# v2.net
KiCad netlist of a schematic drawn in EAGLE
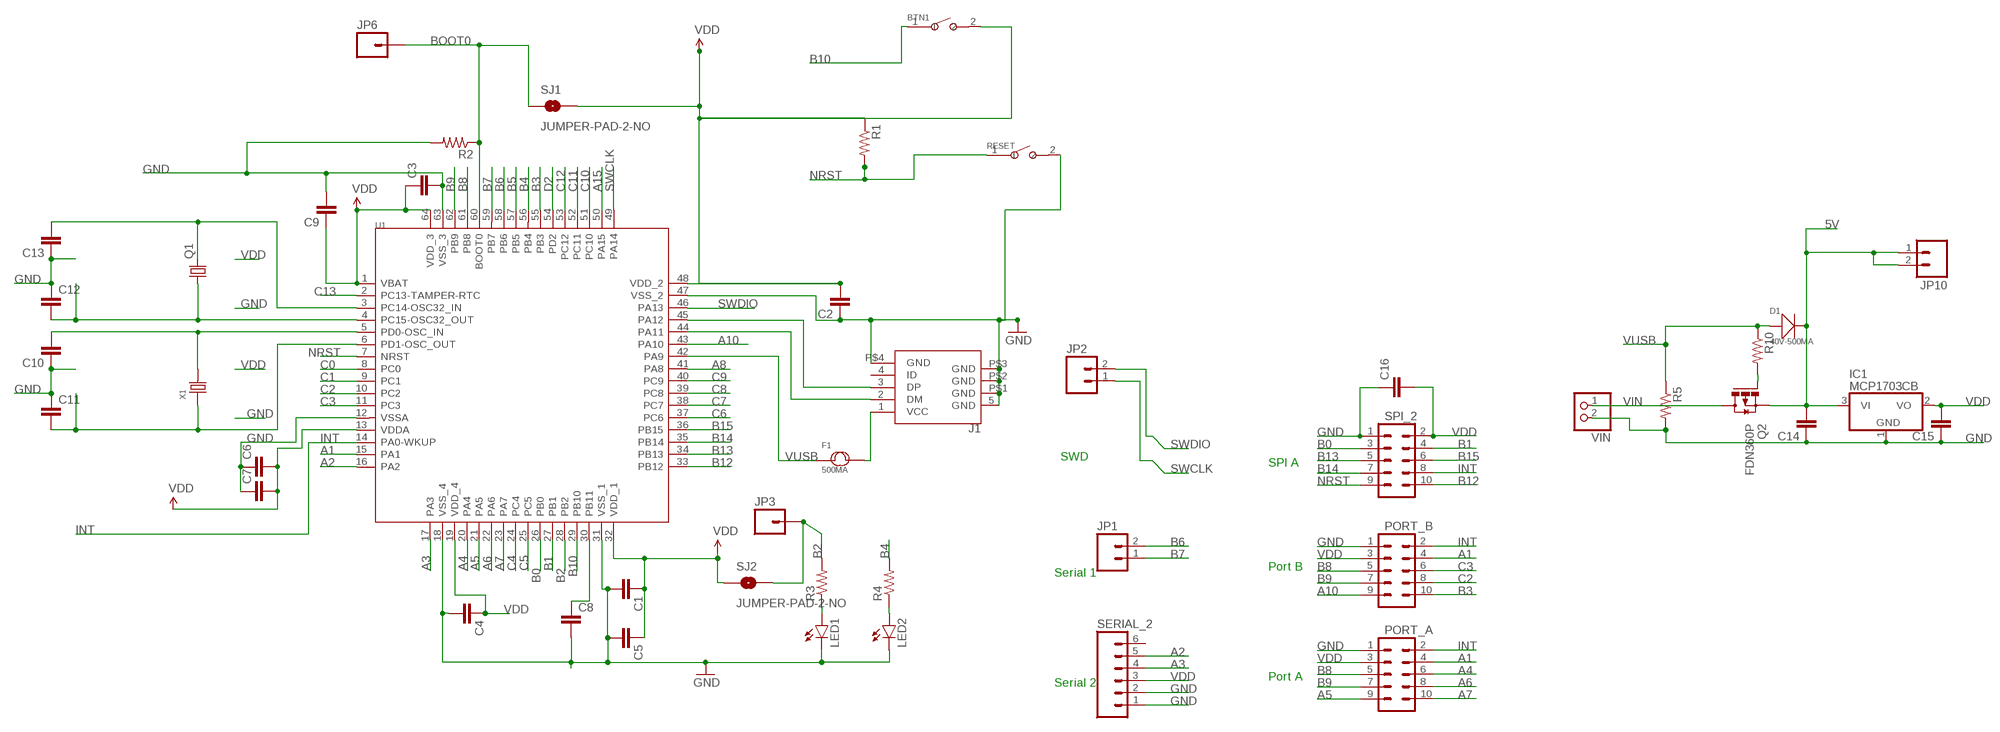
[diagram p0: schematic, sheet 1]

(export (version "E")
  (design (tool "Eeschema 10.0.6"))
  (components
    (comp (ref "BTN1")
      (value "SMD-BUTTON(2P-6.0X3.0X2.5MM)-DHT-1163S")
      (footprint "eagle-import:SW2-4.0-6.0X3.0X2.5MM")
      (libsource (lib "eagle-import") (part "SMD-BUTTON(2P-6.0X3.0X2.5MM)-DHT-1163S"))
    )
    (comp (ref "C1")
      (value "CAP0805")
      (footprint "eagle-import:0805")
      (libsource (lib "eagle-import") (part "CAP0805"))
    )
    (comp (ref "C2")
      (value "CAP0805")
      (footprint "eagle-import:0805")
      (libsource (lib "eagle-import") (part "CAP0805"))
    )
    (comp (ref "C3")
      (value "CAP0805")
      (footprint "eagle-import:0805")
      (libsource (lib "eagle-import") (part "CAP0805"))
    )
    (comp (ref "C4")
      (value "CAP0805")
      (footprint "eagle-import:0805")
      (libsource (lib "eagle-import") (part "CAP0805"))
    )
    (comp (ref "C5")
      (value "CAP0805")
      (footprint "eagle-import:0805")
      (libsource (lib "eagle-import") (part "CAP0805"))
    )
    (comp (ref "C6")
      (value "CAP0805")
      (footprint "eagle-import:0805")
      (libsource (lib "eagle-import") (part "CAP0805"))
    )
    (comp (ref "C7")
      (value "CAP0805")
      (footprint "eagle-import:0805")
      (libsource (lib "eagle-import") (part "CAP0805"))
    )
    (comp (ref "C8")
      (value "CAP0805")
      (footprint "eagle-import:0805")
      (libsource (lib "eagle-import") (part "CAP0805"))
    )
    (comp (ref "C9")
      (value "CAP0805")
      (footprint "eagle-import:0805")
      (libsource (lib "eagle-import") (part "CAP0805"))
    )
    (comp (ref "C10")
      (value "CAP0805")
      (footprint "eagle-import:0805")
      (libsource (lib "eagle-import") (part "CAP0805"))
    )
    (comp (ref "C11")
      (value "CAP0805")
      (footprint "eagle-import:0805")
      (libsource (lib "eagle-import") (part "CAP0805"))
    )
    (comp (ref "C12")
      (value "CAP0805")
      (footprint "eagle-import:0805")
      (libsource (lib "eagle-import") (part "CAP0805"))
    )
    (comp (ref "C13")
      (value "CAP0805")
      (footprint "eagle-import:0805")
      (libsource (lib "eagle-import") (part "CAP0805"))
    )
    (comp (ref "C14")
      (value "CAP0805")
      (footprint "eagle-import:0805")
      (libsource (lib "eagle-import") (part "CAP0805"))
    )
    (comp (ref "C15")
      (value "CAP0805")
      (footprint "eagle-import:0805")
      (libsource (lib "eagle-import") (part "CAP0805"))
    )
    (comp (ref "C16")
      (value "CAP0805")
      (footprint "eagle-import:0805")
      (libsource (lib "eagle-import") (part "CAP0805"))
    )
    (comp (ref "D1")
      (value "40V-500MA")
      (footprint "eagle-import:SOD-123")
      (fields (field (name "MPN") "B0540W"))
      (libsource (lib "eagle-import") (part "SMD-DIODE-SCHOTTKY-40V-500MA(SOD-123)"))
    )
    (comp (ref "F1")
      (value "500MA")
      (footprint "eagle-import:F1206")
      (libsource (lib "eagle-import") (part "SMD-PPTC-500MA(1206)"))
    )
    (comp (ref "IC1")
      (value "MCP1703CB")
      (footprint "eagle-import:SOT23")
      (libsource (lib "eagle-import") (part "MCP1703CB"))
    )
    (comp (ref "J1")
      (value "MINI-USB-RCPT-B-5PS-R/A-SMD(ST-USB-002A)")
      (footprint "eagle-import:MINIUSB5+4P-SMD-0.8-90D")
      (fields (field (name "MPN") "ST-USB-002A"))
      (libsource (lib "eagle-import") (part "MINI-USB-RCPT-B-5PS-R/A-SMD(ST-USB-002A)"))
    )
    (comp (ref "JP1")
      (value "M02PTH")
      (footprint "eagle-import:1X02")
      (libsource (lib "eagle-import") (part "M02PTH"))
    )
    (comp (ref "JP2")
      (value "M02PTH")
      (footprint "eagle-import:1X02")
      (libsource (lib "eagle-import") (part "M02PTH"))
    )
    (comp (ref "JP3")
      (value "M01PTH")
      (footprint "eagle-import:1X01")
      (libsource (lib "eagle-import") (part "M01PTH"))
    )
    (comp (ref "JP6")
      (value "M01PTH")
      (footprint "eagle-import:1X01")
      (libsource (lib "eagle-import") (part "M01PTH"))
    )
    (comp (ref "JP10")
      (value "M02PTH")
      (footprint "eagle-import:1X02")
      (libsource (lib "eagle-import") (part "M02PTH"))
    )
    (comp (ref "LED1")
      (value "LED1206")
      (footprint "eagle-import:LED-1206")
      (libsource (lib "eagle-import") (part "LED1206"))
    )
    (comp (ref "LED2")
      (value "LED1206")
      (footprint "eagle-import:LED-1206")
      (libsource (lib "eagle-import") (part "LED1206"))
    )
    (comp (ref "PORT_A")
      (value "M05X2PTH")
      (footprint "eagle-import:AVR_ICSP")
      (libsource (lib "eagle-import") (part "M05X2PTH"))
    )
    (comp (ref "PORT_B")
      (value "M05X2PTH")
      (footprint "eagle-import:AVR_ICSP")
      (libsource (lib "eagle-import") (part "M05X2PTH"))
    )
    (comp (ref "Q1")
      (value "CRYSTALTC26H")
      (footprint "eagle-import:TC26H")
      (libsource (lib "eagle-import") (part "CRYSTALTC26H"))
    )
    (comp (ref "Q2")
      (value "FDN360P")
      (footprint "eagle-import:SUPER-SOT3")
      (libsource (lib "eagle-import") (part "FDN360P"))
    )
    (comp (ref "R1")
      (value "RESISTOR0805-RES")
      (footprint "eagle-import:0805")
      (libsource (lib "eagle-import") (part "RESISTOR0805-RES"))
    )
    (comp (ref "R2")
      (value "RESISTOR0805-RES")
      (footprint "eagle-import:0805")
      (libsource (lib "eagle-import") (part "RESISTOR0805-RES"))
    )
    (comp (ref "R3")
      (value "RESISTOR0805-RES")
      (footprint "eagle-import:0805")
      (libsource (lib "eagle-import") (part "RESISTOR0805-RES"))
    )
    (comp (ref "R4")
      (value "RESISTOR0805-RES")
      (footprint "eagle-import:0805")
      (libsource (lib "eagle-import") (part "RESISTOR0805-RES"))
    )
    (comp (ref "R5")
      (value "RESISTOR0805-RES")
      (footprint "eagle-import:0805")
      (libsource (lib "eagle-import") (part "RESISTOR0805-RES"))
    )
    (comp (ref "R10")
      (value "RESISTOR0805-RES")
      (footprint "eagle-import:0805")
      (libsource (lib "eagle-import") (part "RESISTOR0805-RES"))
    )
    (comp (ref "RESET")
      (value "SMD-BUTTON(2P-6.0X3.0X2.5MM)-DHT-1163S")
      (footprint "eagle-import:SW2-4.0-6.0X3.0X2.5MM")
      (libsource (lib "eagle-import") (part "SMD-BUTTON(2P-6.0X3.0X2.5MM)-DHT-1163S"))
    )
    (comp (ref "SERIAL_2")
      (value "M06SILK_FEMALE_PTH")
      (footprint "eagle-import:1X06")
      (libsource (lib "eagle-import") (part "M06SILK_FEMALE_PTH"))
    )
    (comp (ref "SJ1")
      (value "JUMPER-PAD-2-NO")
      (footprint "eagle-import:PAD-JUMPER-2-NO_NO_SILK")
      (libsource (lib "eagle-import") (part "JUMPER-PAD-2-NO"))
    )
    (comp (ref "SJ2")
      (value "JUMPER-PAD-2-NO")
      (footprint "eagle-import:PAD-JUMPER-2-NO_NO_SILK")
      (libsource (lib "eagle-import") (part "JUMPER-PAD-2-NO"))
    )
    (comp (ref "SPI_2")
      (value "M05X2PTH")
      (footprint "eagle-import:AVR_ICSP")
      (libsource (lib "eagle-import") (part "M05X2PTH"))
    )
    (comp (ref "U1")
      (value "MCU-STM32F401RBT6(LQFP64)")
      (footprint "eagle-import:LQFP64-0.5-10X10MM")
      (fields (field (name "MPN") "STM32F401RBT6"))
      (libsource (lib "eagle-import") (part "MCU-STM32F401RBT6(LQFP64)"))
    )
    (comp (ref "VIN")
      (value "JST_2PIN-SMT-RA")
      (footprint "eagle-import:JST-PH-2-SMT-RA")
      (libsource (lib "eagle-import") (part "JST_2PIN-SMT-RA"))
    )
    (comp (ref "X1")
      (value "CRYSTAL'HC49US'")
      (footprint "eagle-import:HC49US")
      (libsource (lib "eagle-import") (part "CRYSTAL'HC49US'"))
    )
  )
  (nets
    (net (code "1") (name "/5V") (class "Default")
      (node (ref "C14") (pin "2") (pinfunction "2_2") (pintype "passive"))
      (node (ref "D1") (pin "-") (pinfunction "-_-") (pintype "passive"))
      (node (ref "IC1") (pin "3") (pinfunction "VI_3") (pintype "input"))
      (node (ref "JP10") (pin "1") (pinfunction "1_1") (pintype "passive"))
      (node (ref "JP10") (pin "2") (pinfunction "2_2") (pintype "passive"))
      (node (ref "Q2") (pin "2") (pinfunction "S_2") (pintype "passive"))
    )
    (net (code "2") (name "/A1") (class "Default")
      (node (ref "PORT_A") (pin "4") (pinfunction "4_4") (pintype "passive"))
      (node (ref "PORT_B") (pin "4") (pinfunction "4_4") (pintype "passive"))
      (node (ref "U1") (pin "15") (pinfunction "PA1_15") (pintype "bidirectional"))
    )
    (net (code "3") (name "/A2") (class "Default")
      (node (ref "SERIAL_2") (pin "5") (pinfunction "5_5") (pintype "passive"))
      (node (ref "U1") (pin "16") (pinfunction "PA2_16") (pintype "bidirectional"))
    )
    (net (code "4") (name "/A3") (class "Default")
      (node (ref "SERIAL_2") (pin "4") (pinfunction "4_4") (pintype "passive"))
      (node (ref "U1") (pin "17") (pinfunction "PA3_17") (pintype "bidirectional"))
    )
    (net (code "5") (name "/A4") (class "Default")
      (node (ref "PORT_A") (pin "6") (pinfunction "6_6") (pintype "passive"))
      (node (ref "U1") (pin "20") (pinfunction "PA4_20") (pintype "bidirectional"))
    )
    (net (code "6") (name "/A5") (class "Default")
      (node (ref "PORT_A") (pin "9") (pinfunction "9_9") (pintype "passive"))
      (node (ref "U1") (pin "21") (pinfunction "PA5_21") (pintype "bidirectional"))
    )
    (net (code "7") (name "/A6") (class "Default")
      (node (ref "PORT_A") (pin "8") (pinfunction "8_8") (pintype "passive"))
      (node (ref "U1") (pin "22") (pinfunction "PA6_22") (pintype "bidirectional"))
    )
    (net (code "8") (name "/A7") (class "Default")
      (node (ref "PORT_A") (pin "10") (pinfunction "10_10") (pintype "passive"))
      (node (ref "U1") (pin "23") (pinfunction "PA7_23") (pintype "bidirectional"))
    )
    (net (code "9") (name "/A8") (class "Default")
      (node (ref "U1") (pin "41") (pinfunction "PA8_41") (pintype "bidirectional"))
    )
    (net (code "10") (name "/A10") (class "Default")
      (node (ref "PORT_B") (pin "9") (pinfunction "9_9") (pintype "passive"))
      (node (ref "U1") (pin "43") (pinfunction "PA10_43") (pintype "bidirectional"))
    )
    (net (code "11") (name "/A15") (class "Default")
      (node (ref "U1") (pin "50") (pinfunction "PA15_50") (pintype "bidirectional"))
    )
    (net (code "12") (name "/B0") (class "Default")
      (node (ref "SPI_2") (pin "3") (pinfunction "3_3") (pintype "passive"))
      (node (ref "U1") (pin "26") (pinfunction "PB0_26") (pintype "bidirectional"))
    )
    (net (code "13") (name "/B1") (class "Default")
      (node (ref "SPI_2") (pin "4") (pinfunction "4_4") (pintype "passive"))
      (node (ref "U1") (pin "27") (pinfunction "PB1_27") (pintype "bidirectional"))
    )
    (net (code "14") (name "/B2") (class "Default")
      (node (ref "JP3") (pin "1") (pinfunction "1_1") (pintype "passive"))
      (node (ref "R3") (pin "2") (pinfunction "2_2") (pintype "passive"))
      (node (ref "SJ2") (pin "2") (pinfunction "2_2") (pintype "passive"))
      (node (ref "U1") (pin "28") (pinfunction "PB2_28") (pintype "bidirectional"))
    )
    (net (code "15") (name "/B3") (class "Default")
      (node (ref "PORT_B") (pin "10") (pinfunction "10_10") (pintype "passive"))
      (node (ref "U1") (pin "55") (pinfunction "PB3_55") (pintype "bidirectional"))
    )
    (net (code "16") (name "/B4") (class "Default")
      (node (ref "R4") (pin "2") (pinfunction "2_2") (pintype "passive"))
      (node (ref "U1") (pin "56") (pinfunction "PB4_56") (pintype "bidirectional"))
    )
    (net (code "17") (name "/B5") (class "Default")
      (node (ref "U1") (pin "57") (pinfunction "PB5_57") (pintype "bidirectional"))
    )
    (net (code "18") (name "/B6") (class "Default")
      (node (ref "JP1") (pin "2") (pinfunction "2_2") (pintype "passive"))
      (node (ref "U1") (pin "58") (pinfunction "PB6_58") (pintype "bidirectional"))
    )
    (net (code "19") (name "/B7") (class "Default")
      (node (ref "JP1") (pin "1") (pinfunction "1_1") (pintype "passive"))
      (node (ref "U1") (pin "59") (pinfunction "PB7_59") (pintype "bidirectional"))
    )
    (net (code "20") (name "/B8") (class "Default")
      (node (ref "PORT_A") (pin "5") (pinfunction "5_5") (pintype "passive"))
      (node (ref "PORT_B") (pin "5") (pinfunction "5_5") (pintype "passive"))
      (node (ref "U1") (pin "61") (pinfunction "PB8_61") (pintype "bidirectional"))
    )
    (net (code "21") (name "/B9") (class "Default")
      (node (ref "PORT_A") (pin "7") (pinfunction "7_7") (pintype "passive"))
      (node (ref "PORT_B") (pin "7") (pinfunction "7_7") (pintype "passive"))
      (node (ref "U1") (pin "62") (pinfunction "PB9_62") (pintype "bidirectional"))
    )
    (net (code "22") (name "/B10") (class "Default")
      (node (ref "BTN1") (pin "1") (pinfunction "1_1") (pintype "bidirectional"))
      (node (ref "U1") (pin "29") (pinfunction "PB10_29") (pintype "bidirectional"))
    )
    (net (code "23") (name "/B12") (class "Default")
      (node (ref "SPI_2") (pin "10") (pinfunction "10_10") (pintype "passive"))
      (node (ref "U1") (pin "33") (pinfunction "PB12_33") (pintype "bidirectional"))
    )
    (net (code "24") (name "/B13") (class "Default")
      (node (ref "SPI_2") (pin "5") (pinfunction "5_5") (pintype "passive"))
      (node (ref "U1") (pin "34") (pinfunction "PB13_34") (pintype "bidirectional"))
    )
    (net (code "25") (name "/B14") (class "Default")
      (node (ref "SPI_2") (pin "7") (pinfunction "7_7") (pintype "passive"))
      (node (ref "U1") (pin "35") (pinfunction "PB14_35") (pintype "bidirectional"))
    )
    (net (code "26") (name "/B15") (class "Default")
      (node (ref "SPI_2") (pin "6") (pinfunction "6_6") (pintype "passive"))
      (node (ref "U1") (pin "36") (pinfunction "PB15_36") (pintype "bidirectional"))
    )
    (net (code "27") (name "/BOOT0") (class "Default")
      (node (ref "JP6") (pin "1") (pinfunction "1_1") (pintype "passive"))
      (node (ref "R2") (pin "1") (pinfunction "1_1") (pintype "passive"))
      (node (ref "SJ1") (pin "1") (pinfunction "1_1") (pintype "passive"))
      (node (ref "U1") (pin "60") (pinfunction "BOOT0_60") (pintype "bidirectional"))
    )
    (net (code "28") (name "/C0") (class "Default")
      (node (ref "U1") (pin "8") (pinfunction "PC0_8") (pintype "bidirectional"))
    )
    (net (code "29") (name "/C1") (class "Default")
      (node (ref "U1") (pin "9") (pinfunction "PC1_9") (pintype "bidirectional"))
    )
    (net (code "30") (name "/C2") (class "Default")
      (node (ref "PORT_B") (pin "8") (pinfunction "8_8") (pintype "passive"))
      (node (ref "U1") (pin "10") (pinfunction "PC2_10") (pintype "bidirectional"))
    )
    (net (code "31") (name "/C3") (class "Default")
      (node (ref "PORT_B") (pin "6") (pinfunction "6_6") (pintype "passive"))
      (node (ref "U1") (pin "11") (pinfunction "PC3_11") (pintype "bidirectional"))
    )
    (net (code "32") (name "/C4") (class "Default")
      (node (ref "U1") (pin "24") (pinfunction "PC4_24") (pintype "bidirectional"))
    )
    (net (code "33") (name "/C5") (class "Default")
      (node (ref "U1") (pin "25") (pinfunction "PC5_25") (pintype "bidirectional"))
    )
    (net (code "34") (name "/C6") (class "Default")
      (node (ref "U1") (pin "37") (pinfunction "PC6_37") (pintype "bidirectional"))
    )
    (net (code "35") (name "/C7") (class "Default")
      (node (ref "U1") (pin "38") (pinfunction "PC7_38") (pintype "bidirectional"))
    )
    (net (code "36") (name "/C8") (class "Default")
      (node (ref "U1") (pin "39") (pinfunction "PC8_39") (pintype "bidirectional"))
    )
    (net (code "37") (name "/C9") (class "Default")
      (node (ref "U1") (pin "40") (pinfunction "PC9_40") (pintype "bidirectional"))
    )
    (net (code "38") (name "/C10") (class "Default")
      (node (ref "U1") (pin "51") (pinfunction "PC10_51") (pintype "bidirectional"))
    )
    (net (code "39") (name "/C11") (class "Default")
      (node (ref "U1") (pin "52") (pinfunction "PC11_52") (pintype "bidirectional"))
    )
    (net (code "40") (name "/C12") (class "Default")
      (node (ref "U1") (pin "53") (pinfunction "PC12_53") (pintype "bidirectional"))
    )
    (net (code "41") (name "/C13") (class "Default")
      (node (ref "U1") (pin "2") (pinfunction "PC13-TAMPER-RTC_2") (pintype "bidirectional"))
    )
    (net (code "42") (name "/D2") (class "Default")
      (node (ref "U1") (pin "54") (pinfunction "PD2_54") (pintype "bidirectional"))
    )
    (net (code "43") (name "/INT") (class "Default")
      (node (ref "PORT_A") (pin "2") (pinfunction "2_2") (pintype "passive"))
      (node (ref "PORT_B") (pin "2") (pinfunction "2_2") (pintype "passive"))
      (node (ref "SPI_2") (pin "8") (pinfunction "8_8") (pintype "passive"))
      (node (ref "U1") (pin "14") (pinfunction "PA0-WKUP_14") (pintype "bidirectional"))
    )
    (net (code "44") (name "/NRST") (class "Default")
      (node (ref "R1") (pin "2") (pinfunction "2_2") (pintype "passive"))
      (node (ref "RESET") (pin "1") (pinfunction "1_1") (pintype "bidirectional"))
      (node (ref "SPI_2") (pin "9") (pinfunction "9_9") (pintype "passive"))
      (node (ref "U1") (pin "7") (pinfunction "NRST_7") (pintype "bidirectional"))
    )
    (net (code "45") (name "/SWCLK") (class "Default")
      (node (ref "JP2") (pin "1") (pinfunction "1_1") (pintype "passive"))
      (node (ref "U1") (pin "49") (pinfunction "PA14_49") (pintype "bidirectional"))
    )
    (net (code "46") (name "/SWDIO") (class "Default")
      (node (ref "JP2") (pin "2") (pinfunction "2_2") (pintype "passive"))
      (node (ref "U1") (pin "46") (pinfunction "PA13_46") (pintype "bidirectional"))
    )
    (net (code "47") (name "/VIN") (class "Default")
      (node (ref "Q2") (pin "3") (pinfunction "D_3") (pintype "passive"))
      (node (ref "VIN") (pin "1") (pinfunction "2_1") (pintype "passive"))
    )
    (net (code "48") (name "/VUSB") (class "Default")
      (node (ref "D1") (pin "+") (pinfunction "+_+") (pintype "passive"))
      (node (ref "F1") (pin "1") (pinfunction "1_1") (pintype "bidirectional"))
      (node (ref "R10") (pin "1") (pinfunction "1_1") (pintype "passive"))
      (node (ref "R5") (pin "1") (pinfunction "1_1") (pintype "passive"))
      (node (ref "U1") (pin "42") (pinfunction "PA9_42") (pintype "bidirectional"))
    )
    (net (code "49") (name "GND") (class "Default")
      (node (ref "C1") (pin "2") (pinfunction "2_2") (pintype "passive"))
      (node (ref "C10") (pin "1") (pinfunction "1_1") (pintype "passive"))
      (node (ref "C11") (pin "1") (pinfunction "1_1") (pintype "passive"))
      (node (ref "C12") (pin "1") (pinfunction "1_1") (pintype "passive"))
      (node (ref "C13") (pin "1") (pinfunction "1_1") (pintype "passive"))
      (node (ref "C14") (pin "1") (pinfunction "1_1") (pintype "passive"))
      (node (ref "C15") (pin "1") (pinfunction "1_1") (pintype "passive"))
      (node (ref "C16") (pin "1") (pinfunction "1_1") (pintype "passive"))
      (node (ref "C2") (pin "1") (pinfunction "1_1") (pintype "passive"))
      (node (ref "C3") (pin "2") (pinfunction "2_2") (pintype "passive"))
      (node (ref "C4") (pin "2") (pinfunction "2_2") (pintype "passive"))
      (node (ref "C5") (pin "2") (pinfunction "2_2") (pintype "passive"))
      (node (ref "C6") (pin "1") (pinfunction "1_1") (pintype "passive"))
      (node (ref "C7") (pin "1") (pinfunction "1_1") (pintype "passive"))
      (node (ref "C8") (pin "2") (pinfunction "2_2") (pintype "passive"))
      (node (ref "C9") (pin "2") (pinfunction "2_2") (pintype "passive"))
      (node (ref "IC1") (pin "1") (pinfunction "GND_1") (pintype "passive"))
      (node (ref "J1") (pin "5") (pinfunction "GND_5") (pintype "bidirectional"))
      (node (ref "J1") (pin "P$1") (pinfunction "GND_P$1") (pintype "bidirectional"))
      (node (ref "J1") (pin "P$2") (pinfunction "GND_P$2") (pintype "bidirectional"))
      (node (ref "J1") (pin "P$3") (pinfunction "GND_P$3") (pintype "bidirectional"))
      (node (ref "J1") (pin "P$4") (pinfunction "GND_P$4") (pintype "bidirectional"))
      (node (ref "LED1") (pin "C") (pinfunction "C_C") (pintype "passive"))
      (node (ref "LED2") (pin "C") (pinfunction "C_C") (pintype "passive"))
      (node (ref "PORT_A") (pin "1") (pinfunction "1_1") (pintype "passive"))
      (node (ref "PORT_B") (pin "1") (pinfunction "1_1") (pintype "passive"))
      (node (ref "R2") (pin "2") (pinfunction "2_2") (pintype "passive"))
      (node (ref "R5") (pin "2") (pinfunction "2_2") (pintype "passive"))
      (node (ref "RESET") (pin "2") (pinfunction "2_2") (pintype "bidirectional"))
      (node (ref "SERIAL_2") (pin "1") (pinfunction "1_1") (pintype "passive"))
      (node (ref "SERIAL_2") (pin "2") (pinfunction "2_2") (pintype "passive"))
      (node (ref "SPI_2") (pin "1") (pinfunction "1_1") (pintype "passive"))
      (node (ref "U1") (pin "12") (pinfunction "VSSA_12") (pintype "bidirectional"))
      (node (ref "U1") (pin "18") (pinfunction "VSS_4_18") (pintype "bidirectional"))
      (node (ref "U1") (pin "31") (pinfunction "VSS_1_31") (pintype "bidirectional"))
      (node (ref "U1") (pin "47") (pinfunction "VSS_2_47") (pintype "bidirectional"))
      (node (ref "U1") (pin "63") (pinfunction "VSS_3_63") (pintype "bidirectional"))
      (node (ref "VIN") (pin "2") (pinfunction "1_2") (pintype "passive"))
    )
    (net (code "50") (name "Net-(J1-DM)") (class "Default")
      (node (ref "J1") (pin "2") (pinfunction "DM_2") (pintype "bidirectional"))
      (node (ref "U1") (pin "44") (pinfunction "PA11_44") (pintype "bidirectional"))
    )
    (net (code "51") (name "Net-(J1-DP)") (class "Default")
      (node (ref "J1") (pin "3") (pinfunction "DP_3") (pintype "bidirectional"))
      (node (ref "U1") (pin "45") (pinfunction "PA12_45") (pintype "bidirectional"))
    )
    (net (code "52") (name "Net-(J1-VCC)") (class "Default")
      (node (ref "F1") (pin "2") (pinfunction "2_2") (pintype "bidirectional"))
      (node (ref "J1") (pin "1") (pinfunction "VCC_1") (pintype "bidirectional"))
    )
    (net (code "53") (name "Net-(LED1-PadA)") (class "Default")
      (node (ref "LED1") (pin "A") (pinfunction "A_A") (pintype "passive"))
      (node (ref "R3") (pin "1") (pinfunction "1_1") (pintype "passive"))
    )
    (net (code "54") (name "Net-(LED2-PadA)") (class "Default")
      (node (ref "LED2") (pin "A") (pinfunction "A_A") (pintype "passive"))
      (node (ref "R4") (pin "1") (pinfunction "1_1") (pintype "passive"))
    )
    (net (code "55") (name "Net-(Q2-G)") (class "Default")
      (node (ref "Q2") (pin "1") (pinfunction "G_1") (pintype "passive"))
      (node (ref "R10") (pin "2") (pinfunction "2_2") (pintype "passive"))
    )
    (net (code "56") (name "Net-(U1-PB11)") (class "Default")
      (node (ref "C8") (pin "1") (pinfunction "1_1") (pintype "passive"))
      (node (ref "U1") (pin "30") (pinfunction "PB11_30") (pintype "bidirectional"))
    )
    (net (code "57") (name "Net-(U1-PC14-OSC32_IN)") (class "Default")
      (node (ref "C13") (pin "2") (pinfunction "2_2") (pintype "passive"))
      (node (ref "Q1") (pin "2") (pinfunction "2_2") (pintype "passive"))
      (node (ref "U1") (pin "3") (pinfunction "PC14-OSC32_IN_3") (pintype "bidirectional"))
    )
    (net (code "58") (name "Net-(U1-PC15-OSC32_OUT)") (class "Default")
      (node (ref "C12") (pin "2") (pinfunction "2_2") (pintype "passive"))
      (node (ref "Q1") (pin "1") (pinfunction "1_1") (pintype "passive"))
      (node (ref "U1") (pin "4") (pinfunction "PC15-OSC32_OUT_4") (pintype "bidirectional"))
    )
    (net (code "59") (name "Net-(U1-PD0-OSC_IN)") (class "Default")
      (node (ref "C10") (pin "2") (pinfunction "2_2") (pintype "passive"))
      (node (ref "U1") (pin "5") (pinfunction "PD0-OSC_IN_5") (pintype "bidirectional"))
      (node (ref "X1") (pin "2") (pinfunction "2_2") (pintype "passive"))
    )
    (net (code "60") (name "Net-(U1-PD1-OSC_OUT)") (class "Default")
      (node (ref "C11") (pin "2") (pinfunction "2_2") (pintype "passive"))
      (node (ref "U1") (pin "6") (pinfunction "PD1-OSC_OUT_6") (pintype "bidirectional"))
      (node (ref "X1") (pin "1") (pinfunction "1_1") (pintype "passive"))
    )
    (net (code "61") (name "VDD") (class "Default")
      (node (ref "BTN1") (pin "2") (pinfunction "2_2") (pintype "bidirectional"))
      (node (ref "C1") (pin "1") (pinfunction "1_1") (pintype "passive"))
      (node (ref "C15") (pin "2") (pinfunction "2_2") (pintype "passive"))
      (node (ref "C16") (pin "2") (pinfunction "2_2") (pintype "passive"))
      (node (ref "C2") (pin "2") (pinfunction "2_2") (pintype "passive"))
      (node (ref "C3") (pin "1") (pinfunction "1_1") (pintype "passive"))
      (node (ref "C4") (pin "1") (pinfunction "1_1") (pintype "passive"))
      (node (ref "C5") (pin "1") (pinfunction "1_1") (pintype "passive"))
      (node (ref "C6") (pin "2") (pinfunction "2_2") (pintype "passive"))
      (node (ref "C7") (pin "2") (pinfunction "2_2") (pintype "passive"))
      (node (ref "C9") (pin "1") (pinfunction "1_1") (pintype "passive"))
      (node (ref "IC1") (pin "2") (pinfunction "VO_2") (pintype "passive"))
      (node (ref "PORT_A") (pin "3") (pinfunction "3_3") (pintype "passive"))
      (node (ref "PORT_B") (pin "3") (pinfunction "3_3") (pintype "passive"))
      (node (ref "R1") (pin "1") (pinfunction "1_1") (pintype "passive"))
      (node (ref "SERIAL_2") (pin "3") (pinfunction "3_3") (pintype "passive"))
      (node (ref "SJ1") (pin "2") (pinfunction "2_2") (pintype "passive"))
      (node (ref "SJ2") (pin "1") (pinfunction "1_1") (pintype "passive"))
      (node (ref "SPI_2") (pin "2") (pinfunction "2_2") (pintype "passive"))
      (node (ref "U1") (pin "1") (pinfunction "VBAT_1") (pintype "bidirectional"))
      (node (ref "U1") (pin "13") (pinfunction "VDDA_13") (pintype "bidirectional"))
      (node (ref "U1") (pin "19") (pinfunction "VDD_4_19") (pintype "bidirectional"))
      (node (ref "U1") (pin "32") (pinfunction "VDD_1_32") (pintype "bidirectional"))
      (node (ref "U1") (pin "48") (pinfunction "VDD_2_48") (pintype "bidirectional"))
      (node (ref "U1") (pin "64") (pinfunction "VDD_3_64") (pintype "bidirectional"))
    )
    (net (code "62") (name "unconnected-(J1-ID-Pad4)") (class "Default")
      (node (ref "J1") (pin "4") (pinfunction "ID_4") (pintype "bidirectional"))
    )
    (net (code "63") (name "unconnected-(SERIAL_2-Pad6)") (class "Default")
      (node (ref "SERIAL_2") (pin "6") (pinfunction "6_6") (pintype "passive"))
    )
  )
)
